# tsop_board.net
KiCad netlist of a schematic drawn in Altium Designer
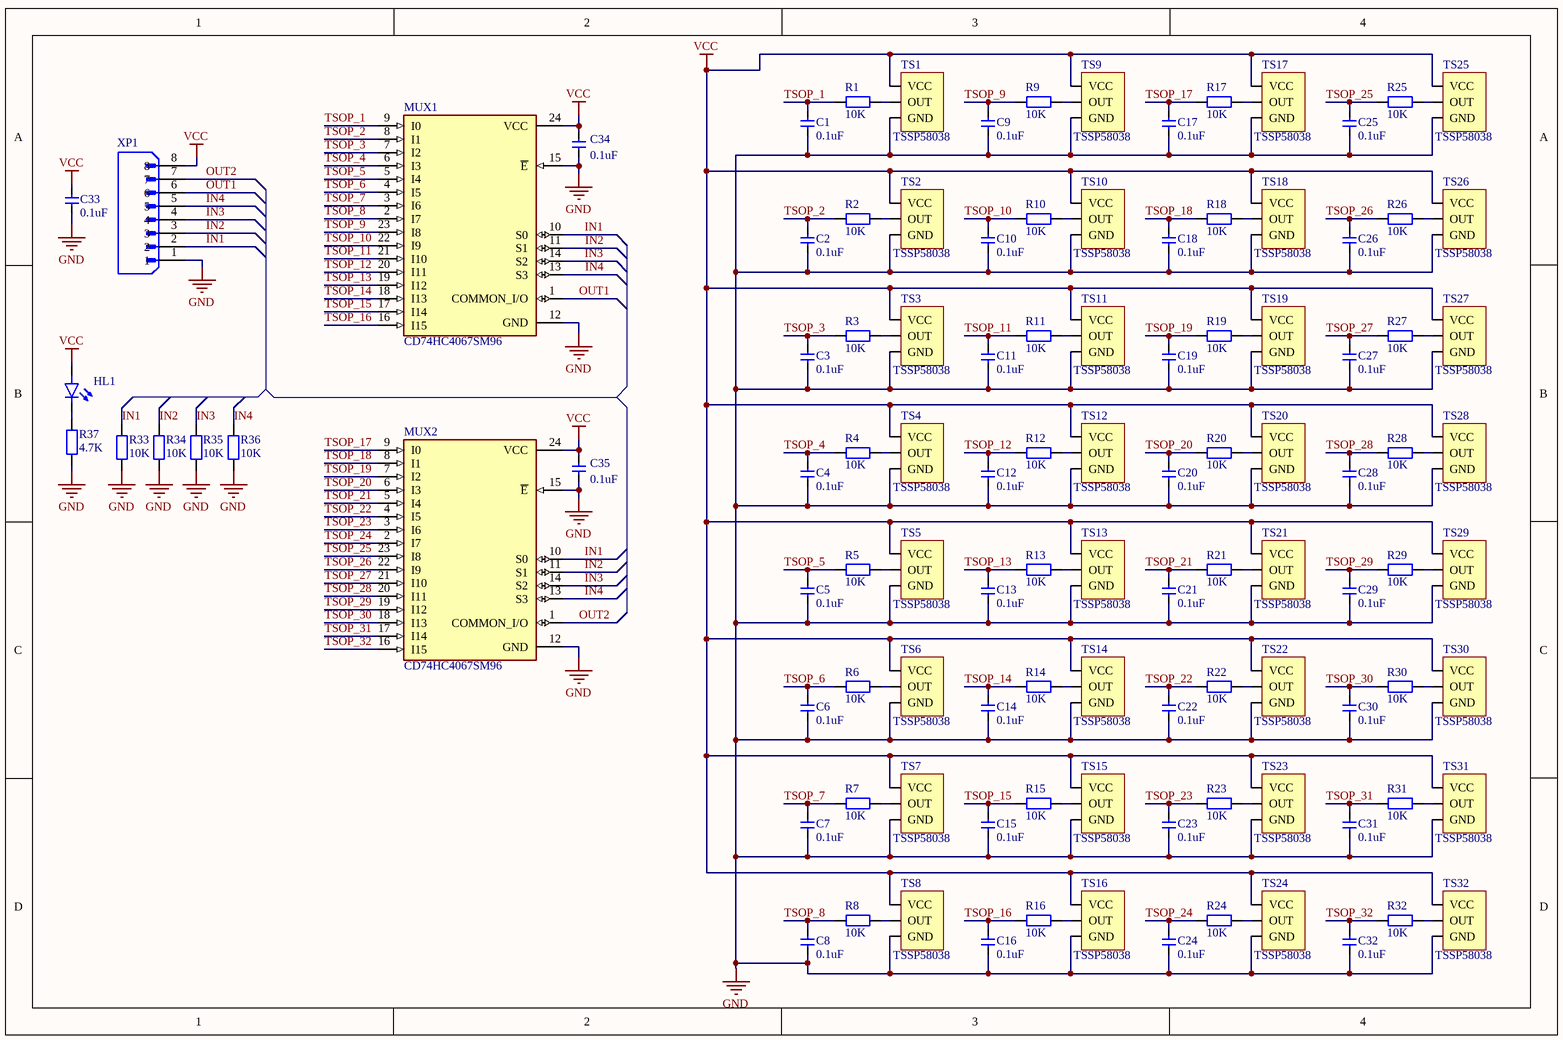
[diagram p0: tsop_board.SchDoc]

(export (version "E")
  (design (tool "Eeschema 10.0.6"))
  (components
    (comp (ref "C1")
      (value "0.1uF")
      (footprint "CAP0805")
      (description "Ceramic SMD Cap")
      (libsource (lib "Asterisk") (part "CAP Ceramic"))
    )
    (comp (ref "C2")
      (value "0.1uF")
      (footprint "CAP0805")
      (description "Ceramic SMD Cap")
      (libsource (lib "Asterisk") (part "CAP Ceramic"))
    )
    (comp (ref "C3")
      (value "0.1uF")
      (footprint "CAP0805")
      (description "Ceramic SMD Cap")
      (libsource (lib "Asterisk") (part "CAP Ceramic"))
    )
    (comp (ref "C4")
      (value "0.1uF")
      (footprint "CAP0805")
      (description "Ceramic SMD Cap")
      (libsource (lib "Asterisk") (part "CAP Ceramic"))
    )
    (comp (ref "C5")
      (value "0.1uF")
      (footprint "CAP0805")
      (description "Ceramic SMD Cap")
      (libsource (lib "Asterisk") (part "CAP Ceramic"))
    )
    (comp (ref "C6")
      (value "0.1uF")
      (footprint "CAP0805")
      (description "Ceramic SMD Cap")
      (libsource (lib "Asterisk") (part "CAP Ceramic"))
    )
    (comp (ref "C7")
      (value "0.1uF")
      (footprint "CAP0805")
      (description "Ceramic SMD Cap")
      (libsource (lib "Asterisk") (part "CAP Ceramic"))
    )
    (comp (ref "C8")
      (value "0.1uF")
      (footprint "CAP0805")
      (description "Ceramic SMD Cap")
      (libsource (lib "Asterisk") (part "CAP Ceramic"))
    )
    (comp (ref "C9")
      (value "0.1uF")
      (footprint "CAP0805")
      (description "Ceramic SMD Cap")
      (libsource (lib "Asterisk") (part "CAP Ceramic"))
    )
    (comp (ref "C10")
      (value "0.1uF")
      (footprint "CAP0805")
      (description "Ceramic SMD Cap")
      (libsource (lib "Asterisk") (part "CAP Ceramic"))
    )
    (comp (ref "C11")
      (value "0.1uF")
      (footprint "CAP0805")
      (description "Ceramic SMD Cap")
      (libsource (lib "Asterisk") (part "CAP Ceramic"))
    )
    (comp (ref "C12")
      (value "0.1uF")
      (footprint "CAP0805")
      (description "Ceramic SMD Cap")
      (libsource (lib "Asterisk") (part "CAP Ceramic"))
    )
    (comp (ref "C13")
      (value "0.1uF")
      (footprint "CAP0805")
      (description "Ceramic SMD Cap")
      (libsource (lib "Asterisk") (part "CAP Ceramic"))
    )
    (comp (ref "C14")
      (value "0.1uF")
      (footprint "CAP0805")
      (description "Ceramic SMD Cap")
      (libsource (lib "Asterisk") (part "CAP Ceramic"))
    )
    (comp (ref "C15")
      (value "0.1uF")
      (footprint "CAP0805")
      (description "Ceramic SMD Cap")
      (libsource (lib "Asterisk") (part "CAP Ceramic"))
    )
    (comp (ref "C16")
      (value "0.1uF")
      (footprint "CAP0805")
      (description "Ceramic SMD Cap")
      (libsource (lib "Asterisk") (part "CAP Ceramic"))
    )
    (comp (ref "C17")
      (value "0.1uF")
      (footprint "CAP0805")
      (description "Ceramic SMD Cap")
      (libsource (lib "Asterisk") (part "CAP Ceramic"))
    )
    (comp (ref "C18")
      (value "0.1uF")
      (footprint "CAP0805")
      (description "Ceramic SMD Cap")
      (libsource (lib "Asterisk") (part "CAP Ceramic"))
    )
    (comp (ref "C19")
      (value "0.1uF")
      (footprint "CAP0805")
      (description "Ceramic SMD Cap")
      (libsource (lib "Asterisk") (part "CAP Ceramic"))
    )
    (comp (ref "C20")
      (value "0.1uF")
      (footprint "CAP0805")
      (description "Ceramic SMD Cap")
      (libsource (lib "Asterisk") (part "CAP Ceramic"))
    )
    (comp (ref "C21")
      (value "0.1uF")
      (footprint "CAP0805")
      (description "Ceramic SMD Cap")
      (libsource (lib "Asterisk") (part "CAP Ceramic"))
    )
    (comp (ref "C22")
      (value "0.1uF")
      (footprint "CAP0805")
      (description "Ceramic SMD Cap")
      (libsource (lib "Asterisk") (part "CAP Ceramic"))
    )
    (comp (ref "C23")
      (value "0.1uF")
      (footprint "CAP0805")
      (description "Ceramic SMD Cap")
      (libsource (lib "Asterisk") (part "CAP Ceramic"))
    )
    (comp (ref "C24")
      (value "0.1uF")
      (footprint "CAP0805")
      (description "Ceramic SMD Cap")
      (libsource (lib "Asterisk") (part "CAP Ceramic"))
    )
    (comp (ref "C25")
      (value "0.1uF")
      (footprint "CAP0805")
      (description "Ceramic SMD Cap")
      (libsource (lib "Asterisk") (part "CAP Ceramic"))
    )
    (comp (ref "C26")
      (value "0.1uF")
      (footprint "CAP0805")
      (description "Ceramic SMD Cap")
      (libsource (lib "Asterisk") (part "CAP Ceramic"))
    )
    (comp (ref "C27")
      (value "0.1uF")
      (footprint "CAP0805")
      (description "Ceramic SMD Cap")
      (libsource (lib "Asterisk") (part "CAP Ceramic"))
    )
    (comp (ref "C28")
      (value "0.1uF")
      (footprint "CAP0805")
      (description "Ceramic SMD Cap")
      (libsource (lib "Asterisk") (part "CAP Ceramic"))
    )
    (comp (ref "C29")
      (value "0.1uF")
      (footprint "CAP0805")
      (description "Ceramic SMD Cap")
      (libsource (lib "Asterisk") (part "CAP Ceramic"))
    )
    (comp (ref "C30")
      (value "0.1uF")
      (footprint "CAP0805")
      (description "Ceramic SMD Cap")
      (libsource (lib "Asterisk") (part "CAP Ceramic"))
    )
    (comp (ref "C31")
      (value "0.1uF")
      (footprint "CAP0805")
      (description "Ceramic SMD Cap")
      (libsource (lib "Asterisk") (part "CAP Ceramic"))
    )
    (comp (ref "C32")
      (value "0.1uF")
      (footprint "CAP0805")
      (description "Ceramic SMD Cap")
      (libsource (lib "Asterisk") (part "CAP Ceramic"))
    )
    (comp (ref "C33")
      (value "0.1uF")
      (footprint "CAP0805")
      (description "Ceramic SMD Cap")
      (libsource (lib "Asterisk") (part "CAP Ceramic"))
    )
    (comp (ref "C34")
      (value "0.1uF")
      (footprint "CAP0805")
      (description "Ceramic SMD Cap")
      (libsource (lib "Asterisk") (part "CAP Ceramic"))
    )
    (comp (ref "C35")
      (value "0.1uF")
      (footprint "CAP0805")
      (description "Ceramic SMD Cap")
      (libsource (lib "Asterisk") (part "CAP Ceramic"))
    )
    (comp (ref "HL1")
      (value "Green")
      (footprint "LED0603_GREEN")
      (description "LED smd")
      (libsource (lib "Asterisk") (part "LED"))
    )
    (comp (ref "MUX1")
      (value "CD74HC4067SM96")
      (footprint "SSOP-24")
      (description "16-channel multiplexer")
      (libsource (lib "Asterisk") (part "CD74HC4067SM96"))
    )
    (comp (ref "MUX2")
      (value "CD74HC4067SM96")
      (footprint "SSOP-24")
      (description "16-channel multiplexer")
      (libsource (lib "Asterisk") (part "CD74HC4067SM96"))
    )
    (comp (ref "R1")
      (value "10K")
      (footprint "RES0805")
      (description "RES smd")
      (libsource (lib "Asterisk") (part "RES"))
    )
    (comp (ref "R2")
      (value "10K")
      (footprint "RES0805")
      (description "RES smd")
      (libsource (lib "Asterisk") (part "RES"))
    )
    (comp (ref "R3")
      (value "10K")
      (footprint "RES0805")
      (description "RES smd")
      (libsource (lib "Asterisk") (part "RES"))
    )
    (comp (ref "R4")
      (value "10K")
      (footprint "RES0805")
      (description "RES smd")
      (libsource (lib "Asterisk") (part "RES"))
    )
    (comp (ref "R5")
      (value "10K")
      (footprint "RES0805")
      (description "RES smd")
      (libsource (lib "Asterisk") (part "RES"))
    )
    (comp (ref "R6")
      (value "10K")
      (footprint "RES0805")
      (description "RES smd")
      (libsource (lib "Asterisk") (part "RES"))
    )
    (comp (ref "R7")
      (value "10K")
      (footprint "RES0805")
      (description "RES smd")
      (libsource (lib "Asterisk") (part "RES"))
    )
    (comp (ref "R8")
      (value "10K")
      (footprint "RES0805")
      (description "RES smd")
      (libsource (lib "Asterisk") (part "RES"))
    )
    (comp (ref "R9")
      (value "10K")
      (footprint "RES0805")
      (description "RES smd")
      (libsource (lib "") (part "RES_1"))
    )
    (comp (ref "R10")
      (value "10K")
      (footprint "RES0805")
      (description "RES smd")
      (libsource (lib "") (part "RES_1"))
    )
    (comp (ref "R11")
      (value "10K")
      (footprint "RES0805")
      (description "RES smd")
      (libsource (lib "") (part "RES_1"))
    )
    (comp (ref "R12")
      (value "10K")
      (footprint "RES0805")
      (description "RES smd")
      (libsource (lib "") (part "RES_1"))
    )
    (comp (ref "R13")
      (value "10K")
      (footprint "RES0805")
      (description "RES smd")
      (libsource (lib "") (part "RES_1"))
    )
    (comp (ref "R14")
      (value "10K")
      (footprint "RES0805")
      (description "RES smd")
      (libsource (lib "") (part "RES_1"))
    )
    (comp (ref "R15")
      (value "10K")
      (footprint "RES0805")
      (description "RES smd")
      (libsource (lib "") (part "RES_1"))
    )
    (comp (ref "R16")
      (value "10K")
      (footprint "RES0805")
      (description "RES smd")
      (libsource (lib "") (part "RES_1"))
    )
    (comp (ref "R17")
      (value "10K")
      (footprint "RES0805")
      (description "RES smd")
      (libsource (lib "Asterisk") (part "RES"))
    )
    (comp (ref "R18")
      (value "10K")
      (footprint "RES0805")
      (description "RES smd")
      (libsource (lib "Asterisk") (part "RES"))
    )
    (comp (ref "R19")
      (value "10K")
      (footprint "RES0805")
      (description "RES smd")
      (libsource (lib "Asterisk") (part "RES"))
    )
    (comp (ref "R20")
      (value "10K")
      (footprint "RES0805")
      (description "RES smd")
      (libsource (lib "Asterisk") (part "RES"))
    )
    (comp (ref "R21")
      (value "10K")
      (footprint "RES0805")
      (description "RES smd")
      (libsource (lib "Asterisk") (part "RES"))
    )
    (comp (ref "R22")
      (value "10K")
      (footprint "RES0805")
      (description "RES smd")
      (libsource (lib "Asterisk") (part "RES"))
    )
    (comp (ref "R23")
      (value "10K")
      (footprint "RES0805")
      (description "RES smd")
      (libsource (lib "Asterisk") (part "RES"))
    )
    (comp (ref "R24")
      (value "10K")
      (footprint "RES0805")
      (description "RES smd")
      (libsource (lib "Asterisk") (part "RES"))
    )
    (comp (ref "R25")
      (value "10K")
      (footprint "RES0805")
      (description "RES smd")
      (libsource (lib "Asterisk") (part "RES"))
    )
    (comp (ref "R26")
      (value "10K")
      (footprint "RES0805")
      (description "RES smd")
      (libsource (lib "Asterisk") (part "RES"))
    )
    (comp (ref "R27")
      (value "10K")
      (footprint "RES0805")
      (description "RES smd")
      (libsource (lib "Asterisk") (part "RES"))
    )
    (comp (ref "R28")
      (value "10K")
      (footprint "RES0805")
      (description "RES smd")
      (libsource (lib "Asterisk") (part "RES"))
    )
    (comp (ref "R29")
      (value "10K")
      (footprint "RES0805")
      (description "RES smd")
      (libsource (lib "Asterisk") (part "RES"))
    )
    (comp (ref "R30")
      (value "10K")
      (footprint "RES0805")
      (description "RES smd")
      (libsource (lib "Asterisk") (part "RES"))
    )
    (comp (ref "R31")
      (value "10K")
      (footprint "RES0805")
      (description "RES smd")
      (libsource (lib "Asterisk") (part "RES"))
    )
    (comp (ref "R32")
      (value "10K")
      (footprint "RES0805")
      (description "RES smd")
      (libsource (lib "Asterisk") (part "RES"))
    )
    (comp (ref "R33")
      (value "10K")
      (footprint "RES0805")
      (description "RES smd")
      (libsource (lib "Asterisk") (part "RES"))
    )
    (comp (ref "R34")
      (value "10K")
      (footprint "RES0805")
      (description "RES smd")
      (libsource (lib "Asterisk") (part "RES"))
    )
    (comp (ref "R35")
      (value "10K")
      (footprint "RES0805")
      (description "RES smd")
      (libsource (lib "Asterisk") (part "RES"))
    )
    (comp (ref "R36")
      (value "10K")
      (footprint "RES0805")
      (description "RES smd")
      (libsource (lib "Asterisk") (part "RES"))
    )
    (comp (ref "R37")
      (value "4.7K")
      (footprint "RES0805")
      (description "RES smd")
      (libsource (lib "Asterisk") (part "RES"))
    )
    (comp (ref "TS1")
      (value "TSSP58038")
      (footprint "TSSP58038 (clear)")
      (description "TSOP TSSP58038")
      (libsource (lib "Asterisk") (part "TSSP58038"))
    )
    (comp (ref "TS2")
      (value "TSSP58038")
      (footprint "TSSP58038 (clear)")
      (description "TSOP TSSP58038")
      (libsource (lib "Asterisk") (part "TSSP58038"))
    )
    (comp (ref "TS3")
      (value "TSSP58038")
      (footprint "TSSP58038 (clear)")
      (description "TSOP TSSP58038")
      (libsource (lib "Asterisk") (part "TSSP58038"))
    )
    (comp (ref "TS4")
      (value "TSSP58038")
      (footprint "TSSP58038 (clear)")
      (description "TSOP TSSP58038")
      (libsource (lib "Asterisk") (part "TSSP58038"))
    )
    (comp (ref "TS5")
      (value "TSSP58038")
      (footprint "TSSP58038 (clear)")
      (description "TSOP TSSP58038")
      (libsource (lib "Asterisk") (part "TSSP58038"))
    )
    (comp (ref "TS6")
      (value "TSSP58038")
      (footprint "TSSP58038 (clear)")
      (description "TSOP TSSP58038")
      (libsource (lib "Asterisk") (part "TSSP58038"))
    )
    (comp (ref "TS7")
      (value "TSSP58038")
      (footprint "TSSP58038 (clear)")
      (description "TSOP TSSP58038")
      (libsource (lib "Asterisk") (part "TSSP58038"))
    )
    (comp (ref "TS8")
      (value "TSSP58038")
      (footprint "TSSP58038 (clear)")
      (description "TSOP TSSP58038")
      (libsource (lib "Asterisk") (part "TSSP58038"))
    )
    (comp (ref "TS9")
      (value "TSSP58038")
      (footprint "TSSP58038 (clear)")
      (description "TSOP TSSP58038")
      (libsource (lib "Asterisk") (part "TSSP58038"))
    )
    (comp (ref "TS10")
      (value "TSSP58038")
      (footprint "TSSP58038 (clear)")
      (description "TSOP TSSP58038")
      (libsource (lib "Asterisk") (part "TSSP58038"))
    )
    (comp (ref "TS11")
      (value "TSSP58038")
      (footprint "TSSP58038 (clear)")
      (description "TSOP TSSP58038")
      (libsource (lib "Asterisk") (part "TSSP58038"))
    )
    (comp (ref "TS12")
      (value "TSSP58038")
      (footprint "TSSP58038 (clear)")
      (description "TSOP TSSP58038")
      (libsource (lib "Asterisk") (part "TSSP58038"))
    )
    (comp (ref "TS13")
      (value "TSSP58038")
      (footprint "TSSP58038 (clear)")
      (description "TSOP TSSP58038")
      (libsource (lib "Asterisk") (part "TSSP58038"))
    )
    (comp (ref "TS14")
      (value "TSSP58038")
      (footprint "TSSP58038 (clear)")
      (description "TSOP TSSP58038")
      (libsource (lib "Asterisk") (part "TSSP58038"))
    )
    (comp (ref "TS15")
      (value "TSSP58038")
      (footprint "TSSP58038 (clear)")
      (description "TSOP TSSP58038")
      (libsource (lib "Asterisk") (part "TSSP58038"))
    )
    (comp (ref "TS16")
      (value "TSSP58038")
      (footprint "TSSP58038 (clear)")
      (description "TSOP TSSP58038")
      (libsource (lib "Asterisk") (part "TSSP58038"))
    )
    (comp (ref "TS17")
      (value "TSSP58038")
      (footprint "TSSP58038 (clear)")
      (description "TSOP TSSP58038")
      (libsource (lib "Asterisk") (part "TSSP58038"))
    )
    (comp (ref "TS18")
      (value "TSSP58038")
      (footprint "TSSP58038 (clear)")
      (description "TSOP TSSP58038")
      (libsource (lib "Asterisk") (part "TSSP58038"))
    )
    (comp (ref "TS19")
      (value "TSSP58038")
      (footprint "TSSP58038 (clear)")
      (description "TSOP TSSP58038")
      (libsource (lib "Asterisk") (part "TSSP58038"))
    )
    (comp (ref "TS20")
      (value "TSSP58038")
      (footprint "TSSP58038 (clear)")
      (description "TSOP TSSP58038")
      (libsource (lib "Asterisk") (part "TSSP58038"))
    )
    (comp (ref "TS21")
      (value "TSSP58038")
      (footprint "TSSP58038 (clear)")
      (description "TSOP TSSP58038")
      (libsource (lib "Asterisk") (part "TSSP58038"))
    )
    (comp (ref "TS22")
      (value "TSSP58038")
      (footprint "TSSP58038 (clear)")
      (description "TSOP TSSP58038")
      (libsource (lib "Asterisk") (part "TSSP58038"))
    )
    (comp (ref "TS23")
      (value "TSSP58038")
      (footprint "TSSP58038 (clear)")
      (description "TSOP TSSP58038")
      (libsource (lib "Asterisk") (part "TSSP58038"))
    )
    (comp (ref "TS24")
      (value "TSSP58038")
      (footprint "TSSP58038 (clear)")
      (description "TSOP TSSP58038")
      (libsource (lib "Asterisk") (part "TSSP58038"))
    )
    (comp (ref "TS25")
      (value "TSSP58038")
      (footprint "TSSP58038 (clear)")
      (description "TSOP TSSP58038")
      (libsource (lib "Asterisk") (part "TSSP58038"))
    )
    (comp (ref "TS26")
      (value "TSSP58038")
      (footprint "TSSP58038 (clear)")
      (description "TSOP TSSP58038")
      (libsource (lib "Asterisk") (part "TSSP58038"))
    )
    (comp (ref "TS27")
      (value "TSSP58038")
      (footprint "TSSP58038 (clear)")
      (description "TSOP TSSP58038")
      (libsource (lib "Asterisk") (part "TSSP58038"))
    )
    (comp (ref "TS28")
      (value "TSSP58038")
      (footprint "TSSP58038 (clear)")
      (description "TSOP TSSP58038")
      (libsource (lib "Asterisk") (part "TSSP58038"))
    )
    (comp (ref "TS29")
      (value "TSSP58038")
      (footprint "TSSP58038 (clear)")
      (description "TSOP TSSP58038")
      (libsource (lib "Asterisk") (part "TSSP58038"))
    )
    (comp (ref "TS30")
      (value "TSSP58038")
      (footprint "TSSP58038 (clear)")
      (description "TSOP TSSP58038")
      (libsource (lib "Asterisk") (part "TSSP58038"))
    )
    (comp (ref "TS31")
      (value "TSSP58038")
      (footprint "TSSP58038 (clear)")
      (description "TSOP TSSP58038")
      (libsource (lib "Asterisk") (part "TSSP58038"))
    )
    (comp (ref "TS32")
      (value "TSSP58038")
      (footprint "TSSP58038 (clear)")
      (description "TSOP TSSP58038")
      (libsource (lib "Asterisk") (part "TSSP58038"))
    )
    (comp (ref "XP1")
      (value "JST_B8B-XH-A(LF)(SN)")
      (footprint "JST_XH-8")
      (description "TSOP Board")
      (libsource (lib "Asterisk") (part "JST-XH-8"))
    )
  )
  (nets
    (net (code "1") (name "/IN1") (class "Default")
      (node (ref "MUX1") (pin "10") (pinfunction "S0_10") (pintype "bidirectional"))
      (node (ref "MUX2") (pin "10") (pinfunction "S0_10") (pintype "bidirectional"))
      (node (ref "R33") (pin "2") (pinfunction "2_2") (pintype "passive"))
      (node (ref "XP1") (pin "2") (pinfunction "2_2") (pintype "passive"))
    )
    (net (code "2") (name "/IN2") (class "Default")
      (node (ref "MUX1") (pin "11") (pinfunction "S1_11") (pintype "bidirectional"))
      (node (ref "MUX2") (pin "11") (pinfunction "S1_11") (pintype "bidirectional"))
      (node (ref "R34") (pin "2") (pinfunction "2_2") (pintype "passive"))
      (node (ref "XP1") (pin "3") (pinfunction "3_3") (pintype "passive"))
    )
    (net (code "3") (name "/IN3") (class "Default")
      (node (ref "MUX1") (pin "14") (pinfunction "S2_14") (pintype "bidirectional"))
      (node (ref "MUX2") (pin "14") (pinfunction "S2_14") (pintype "bidirectional"))
      (node (ref "R35") (pin "2") (pinfunction "2_2") (pintype "passive"))
      (node (ref "XP1") (pin "4") (pinfunction "4_4") (pintype "passive"))
    )
    (net (code "4") (name "/IN4") (class "Default")
      (node (ref "MUX1") (pin "13") (pinfunction "S3_13") (pintype "bidirectional"))
      (node (ref "MUX2") (pin "13") (pinfunction "S3_13") (pintype "bidirectional"))
      (node (ref "R36") (pin "2") (pinfunction "2_2") (pintype "passive"))
      (node (ref "XP1") (pin "5") (pinfunction "5_5") (pintype "passive"))
    )
    (net (code "5") (name "/OUT1") (class "Default")
      (node (ref "MUX1") (pin "1") (pinfunction "COMMON_I/O_1") (pintype "bidirectional"))
      (node (ref "XP1") (pin "6") (pinfunction "6_6") (pintype "passive"))
    )
    (net (code "6") (name "/OUT2") (class "Default")
      (node (ref "MUX2") (pin "1") (pinfunction "COMMON_I/O_1") (pintype "bidirectional"))
      (node (ref "XP1") (pin "7") (pinfunction "7_7") (pintype "passive"))
    )
    (net (code "7") (name "/TSOP_1") (class "Default")
      (node (ref "C1") (pin "2") (pinfunction "2_2") (pintype "passive"))
      (node (ref "MUX1") (pin "9") (pinfunction "I0_9") (pintype "input"))
      (node (ref "R1") (pin "1") (pinfunction "1_1") (pintype "passive"))
    )
    (net (code "8") (name "/TSOP_2") (class "Default")
      (node (ref "C2") (pin "2") (pinfunction "2_2") (pintype "passive"))
      (node (ref "MUX1") (pin "8") (pinfunction "I1_8") (pintype "input"))
      (node (ref "R2") (pin "1") (pinfunction "1_1") (pintype "passive"))
    )
    (net (code "9") (name "/TSOP_3") (class "Default")
      (node (ref "C3") (pin "2") (pinfunction "2_2") (pintype "passive"))
      (node (ref "MUX1") (pin "7") (pinfunction "I2_7") (pintype "input"))
      (node (ref "R3") (pin "1") (pinfunction "1_1") (pintype "passive"))
    )
    (net (code "10") (name "/TSOP_4") (class "Default")
      (node (ref "C4") (pin "2") (pinfunction "2_2") (pintype "passive"))
      (node (ref "MUX1") (pin "6") (pinfunction "I3_6") (pintype "input"))
      (node (ref "R4") (pin "1") (pinfunction "1_1") (pintype "passive"))
    )
    (net (code "11") (name "/TSOP_5") (class "Default")
      (node (ref "C5") (pin "2") (pinfunction "2_2") (pintype "passive"))
      (node (ref "MUX1") (pin "5") (pinfunction "I4_5") (pintype "input"))
      (node (ref "R5") (pin "1") (pinfunction "1_1") (pintype "passive"))
    )
    (net (code "12") (name "/TSOP_6") (class "Default")
      (node (ref "C6") (pin "2") (pinfunction "2_2") (pintype "passive"))
      (node (ref "MUX1") (pin "4") (pinfunction "I5_4") (pintype "input"))
      (node (ref "R6") (pin "1") (pinfunction "1_1") (pintype "passive"))
    )
    (net (code "13") (name "/TSOP_7") (class "Default")
      (node (ref "C7") (pin "2") (pinfunction "2_2") (pintype "passive"))
      (node (ref "MUX1") (pin "3") (pinfunction "I6_3") (pintype "input"))
      (node (ref "R7") (pin "1") (pinfunction "1_1") (pintype "passive"))
    )
    (net (code "14") (name "/TSOP_8") (class "Default")
      (node (ref "C8") (pin "2") (pinfunction "2_2") (pintype "passive"))
      (node (ref "MUX1") (pin "2") (pinfunction "I7_2") (pintype "input"))
      (node (ref "R8") (pin "1") (pinfunction "1_1") (pintype "passive"))
    )
    (net (code "15") (name "/TSOP_9") (class "Default")
      (node (ref "C9") (pin "2") (pinfunction "2_2") (pintype "passive"))
      (node (ref "MUX1") (pin "23") (pinfunction "I8_23") (pintype "input"))
      (node (ref "R9") (pin "1") (pinfunction "1_1") (pintype "passive"))
    )
    (net (code "16") (name "/TSOP_10") (class "Default")
      (node (ref "C10") (pin "2") (pinfunction "2_2") (pintype "passive"))
      (node (ref "MUX1") (pin "22") (pinfunction "I9_22") (pintype "input"))
      (node (ref "R10") (pin "1") (pinfunction "1_1") (pintype "passive"))
    )
    (net (code "17") (name "/TSOP_11") (class "Default")
      (node (ref "C11") (pin "2") (pinfunction "2_2") (pintype "passive"))
      (node (ref "MUX1") (pin "21") (pinfunction "I10_21") (pintype "input"))
      (node (ref "R11") (pin "1") (pinfunction "1_1") (pintype "passive"))
    )
    (net (code "18") (name "/TSOP_12") (class "Default")
      (node (ref "C12") (pin "2") (pinfunction "2_2") (pintype "passive"))
      (node (ref "MUX1") (pin "20") (pinfunction "I11_20") (pintype "input"))
      (node (ref "R12") (pin "1") (pinfunction "1_1") (pintype "passive"))
    )
    (net (code "19") (name "/TSOP_13") (class "Default")
      (node (ref "C13") (pin "2") (pinfunction "2_2") (pintype "passive"))
      (node (ref "MUX1") (pin "19") (pinfunction "I12_19") (pintype "input"))
      (node (ref "R13") (pin "1") (pinfunction "1_1") (pintype "passive"))
    )
    (net (code "20") (name "/TSOP_14") (class "Default")
      (node (ref "C14") (pin "2") (pinfunction "2_2") (pintype "passive"))
      (node (ref "MUX1") (pin "18") (pinfunction "I13_18") (pintype "input"))
      (node (ref "R14") (pin "1") (pinfunction "1_1") (pintype "passive"))
    )
    (net (code "21") (name "/TSOP_15") (class "Default")
      (node (ref "C15") (pin "2") (pinfunction "2_2") (pintype "passive"))
      (node (ref "MUX1") (pin "17") (pinfunction "I14_17") (pintype "input"))
      (node (ref "R15") (pin "1") (pinfunction "1_1") (pintype "passive"))
    )
    (net (code "22") (name "/TSOP_16") (class "Default")
      (node (ref "C16") (pin "2") (pinfunction "2_2") (pintype "passive"))
      (node (ref "MUX1") (pin "16") (pinfunction "I15_16") (pintype "input"))
      (node (ref "R16") (pin "1") (pinfunction "1_1") (pintype "passive"))
    )
    (net (code "23") (name "/TSOP_17") (class "Default")
      (node (ref "C17") (pin "2") (pinfunction "2_2") (pintype "passive"))
      (node (ref "MUX2") (pin "9") (pinfunction "I0_9") (pintype "input"))
      (node (ref "R17") (pin "1") (pinfunction "1_1") (pintype "passive"))
    )
    (net (code "24") (name "/TSOP_18") (class "Default")
      (node (ref "C18") (pin "2") (pinfunction "2_2") (pintype "passive"))
      (node (ref "MUX2") (pin "8") (pinfunction "I1_8") (pintype "input"))
      (node (ref "R18") (pin "1") (pinfunction "1_1") (pintype "passive"))
    )
    (net (code "25") (name "/TSOP_19") (class "Default")
      (node (ref "C19") (pin "2") (pinfunction "2_2") (pintype "passive"))
      (node (ref "MUX2") (pin "7") (pinfunction "I2_7") (pintype "input"))
      (node (ref "R19") (pin "1") (pinfunction "1_1") (pintype "passive"))
    )
    (net (code "26") (name "/TSOP_20") (class "Default")
      (node (ref "C20") (pin "2") (pinfunction "2_2") (pintype "passive"))
      (node (ref "MUX2") (pin "6") (pinfunction "I3_6") (pintype "input"))
      (node (ref "R20") (pin "1") (pinfunction "1_1") (pintype "passive"))
    )
    (net (code "27") (name "/TSOP_21") (class "Default")
      (node (ref "C21") (pin "2") (pinfunction "2_2") (pintype "passive"))
      (node (ref "MUX2") (pin "5") (pinfunction "I4_5") (pintype "input"))
      (node (ref "R21") (pin "1") (pinfunction "1_1") (pintype "passive"))
    )
    (net (code "28") (name "/TSOP_22") (class "Default")
      (node (ref "C22") (pin "2") (pinfunction "2_2") (pintype "passive"))
      (node (ref "MUX2") (pin "4") (pinfunction "I5_4") (pintype "input"))
      (node (ref "R22") (pin "1") (pinfunction "1_1") (pintype "passive"))
    )
    (net (code "29") (name "/TSOP_23") (class "Default")
      (node (ref "C23") (pin "2") (pinfunction "2_2") (pintype "passive"))
      (node (ref "MUX2") (pin "3") (pinfunction "I6_3") (pintype "input"))
      (node (ref "R23") (pin "1") (pinfunction "1_1") (pintype "passive"))
    )
    (net (code "30") (name "/TSOP_24") (class "Default")
      (node (ref "C24") (pin "2") (pinfunction "2_2") (pintype "passive"))
      (node (ref "MUX2") (pin "2") (pinfunction "I7_2") (pintype "input"))
      (node (ref "R24") (pin "1") (pinfunction "1_1") (pintype "passive"))
    )
    (net (code "31") (name "/TSOP_25") (class "Default")
      (node (ref "C25") (pin "2") (pinfunction "2_2") (pintype "passive"))
      (node (ref "MUX2") (pin "23") (pinfunction "I8_23") (pintype "input"))
      (node (ref "R25") (pin "1") (pinfunction "1_1") (pintype "passive"))
    )
    (net (code "32") (name "/TSOP_26") (class "Default")
      (node (ref "C26") (pin "2") (pinfunction "2_2") (pintype "passive"))
      (node (ref "MUX2") (pin "22") (pinfunction "I9_22") (pintype "input"))
      (node (ref "R26") (pin "1") (pinfunction "1_1") (pintype "passive"))
    )
    (net (code "33") (name "/TSOP_27") (class "Default")
      (node (ref "C27") (pin "2") (pinfunction "2_2") (pintype "passive"))
      (node (ref "MUX2") (pin "21") (pinfunction "I10_21") (pintype "input"))
      (node (ref "R27") (pin "1") (pinfunction "1_1") (pintype "passive"))
    )
    (net (code "34") (name "/TSOP_28") (class "Default")
      (node (ref "C28") (pin "2") (pinfunction "2_2") (pintype "passive"))
      (node (ref "MUX2") (pin "20") (pinfunction "I11_20") (pintype "input"))
      (node (ref "R28") (pin "1") (pinfunction "1_1") (pintype "passive"))
    )
    (net (code "35") (name "/TSOP_29") (class "Default")
      (node (ref "C29") (pin "2") (pinfunction "2_2") (pintype "passive"))
      (node (ref "MUX2") (pin "19") (pinfunction "I12_19") (pintype "input"))
      (node (ref "R29") (pin "1") (pinfunction "1_1") (pintype "passive"))
    )
    (net (code "36") (name "/TSOP_30") (class "Default")
      (node (ref "C30") (pin "2") (pinfunction "2_2") (pintype "passive"))
      (node (ref "MUX2") (pin "18") (pinfunction "I13_18") (pintype "input"))
      (node (ref "R30") (pin "1") (pinfunction "1_1") (pintype "passive"))
    )
    (net (code "37") (name "/TSOP_31") (class "Default")
      (node (ref "C31") (pin "2") (pinfunction "2_2") (pintype "passive"))
      (node (ref "MUX2") (pin "17") (pinfunction "I14_17") (pintype "input"))
      (node (ref "R31") (pin "1") (pinfunction "1_1") (pintype "passive"))
    )
    (net (code "38") (name "/TSOP_32") (class "Default")
      (node (ref "C32") (pin "2") (pinfunction "2_2") (pintype "passive"))
      (node (ref "MUX2") (pin "16") (pinfunction "I15_16") (pintype "input"))
      (node (ref "R32") (pin "1") (pinfunction "1_1") (pintype "passive"))
    )
    (net (code "39") (name "GND") (class "Default")
      (node (ref "C1") (pin "1") (pinfunction "1_1") (pintype "passive"))
      (node (ref "C10") (pin "1") (pinfunction "1_1") (pintype "passive"))
      (node (ref "C11") (pin "1") (pinfunction "1_1") (pintype "passive"))
      (node (ref "C12") (pin "1") (pinfunction "1_1") (pintype "passive"))
      (node (ref "C13") (pin "1") (pinfunction "1_1") (pintype "passive"))
      (node (ref "C14") (pin "1") (pinfunction "1_1") (pintype "passive"))
      (node (ref "C15") (pin "1") (pinfunction "1_1") (pintype "passive"))
      (node (ref "C16") (pin "1") (pinfunction "1_1") (pintype "passive"))
      (node (ref "C17") (pin "1") (pinfunction "1_1") (pintype "passive"))
      (node (ref "C18") (pin "1") (pinfunction "1_1") (pintype "passive"))
      (node (ref "C19") (pin "1") (pinfunction "1_1") (pintype "passive"))
      (node (ref "C2") (pin "1") (pinfunction "1_1") (pintype "passive"))
      (node (ref "C20") (pin "1") (pinfunction "1_1") (pintype "passive"))
      (node (ref "C21") (pin "1") (pinfunction "1_1") (pintype "passive"))
      (node (ref "C22") (pin "1") (pinfunction "1_1") (pintype "passive"))
      (node (ref "C23") (pin "1") (pinfunction "1_1") (pintype "passive"))
      (node (ref "C24") (pin "1") (pinfunction "1_1") (pintype "passive"))
      (node (ref "C25") (pin "1") (pinfunction "1_1") (pintype "passive"))
      (node (ref "C26") (pin "1") (pinfunction "1_1") (pintype "passive"))
      (node (ref "C27") (pin "1") (pinfunction "1_1") (pintype "passive"))
      (node (ref "C28") (pin "1") (pinfunction "1_1") (pintype "passive"))
      (node (ref "C29") (pin "1") (pinfunction "1_1") (pintype "passive"))
      (node (ref "C3") (pin "1") (pinfunction "1_1") (pintype "passive"))
      (node (ref "C30") (pin "1") (pinfunction "1_1") (pintype "passive"))
      (node (ref "C31") (pin "1") (pinfunction "1_1") (pintype "passive"))
      (node (ref "C32") (pin "1") (pinfunction "1_1") (pintype "passive"))
      (node (ref "C33") (pin "1") (pinfunction "1_1") (pintype "passive"))
      (node (ref "C34") (pin "1") (pinfunction "1_1") (pintype "passive"))
      (node (ref "C35") (pin "1") (pinfunction "1_1") (pintype "passive"))
      (node (ref "C4") (pin "1") (pinfunction "1_1") (pintype "passive"))
      (node (ref "C5") (pin "1") (pinfunction "1_1") (pintype "passive"))
      (node (ref "C6") (pin "1") (pinfunction "1_1") (pintype "passive"))
      (node (ref "C7") (pin "1") (pinfunction "1_1") (pintype "passive"))
      (node (ref "C8") (pin "1") (pinfunction "1_1") (pintype "passive"))
      (node (ref "C9") (pin "1") (pinfunction "1_1") (pintype "passive"))
      (node (ref "MUX1") (pin "12") (pinfunction "GND_12") (pintype "power_in"))
      (node (ref "MUX1") (pin "15") (pinfunction "~{E}_15") (pintype "input"))
      (node (ref "MUX2") (pin "12") (pinfunction "GND_12") (pintype "power_in"))
      (node (ref "MUX2") (pin "15") (pinfunction "~{E}_15") (pintype "input"))
      (node (ref "R33") (pin "1") (pinfunction "1_1") (pintype "passive"))
      (node (ref "R34") (pin "1") (pinfunction "1_1") (pintype "passive"))
      (node (ref "R35") (pin "1") (pinfunction "1_1") (pintype "passive"))
      (node (ref "R36") (pin "1") (pinfunction "1_1") (pintype "passive"))
      (node (ref "R37") (pin "1") (pinfunction "1_1") (pintype "passive"))
      (node (ref "TS1") (pin "2") (pinfunction "GND_2") (pintype "passive"))
      (node (ref "TS10") (pin "2") (pinfunction "GND_2") (pintype "passive"))
      (node (ref "TS11") (pin "2") (pinfunction "GND_2") (pintype "passive"))
      (node (ref "TS12") (pin "2") (pinfunction "GND_2") (pintype "passive"))
      (node (ref "TS13") (pin "2") (pinfunction "GND_2") (pintype "passive"))
      (node (ref "TS14") (pin "2") (pinfunction "GND_2") (pintype "passive"))
      (node (ref "TS15") (pin "2") (pinfunction "GND_2") (pintype "passive"))
      (node (ref "TS16") (pin "2") (pinfunction "GND_2") (pintype "passive"))
      (node (ref "TS17") (pin "2") (pinfunction "GND_2") (pintype "passive"))
      (node (ref "TS18") (pin "2") (pinfunction "GND_2") (pintype "passive"))
      (node (ref "TS19") (pin "2") (pinfunction "GND_2") (pintype "passive"))
      (node (ref "TS2") (pin "2") (pinfunction "GND_2") (pintype "passive"))
      (node (ref "TS20") (pin "2") (pinfunction "GND_2") (pintype "passive"))
      (node (ref "TS21") (pin "2") (pinfunction "GND_2") (pintype "passive"))
      (node (ref "TS22") (pin "2") (pinfunction "GND_2") (pintype "passive"))
      (node (ref "TS23") (pin "2") (pinfunction "GND_2") (pintype "passive"))
      (node (ref "TS24") (pin "2") (pinfunction "GND_2") (pintype "passive"))
      (node (ref "TS25") (pin "2") (pinfunction "GND_2") (pintype "passive"))
      (node (ref "TS26") (pin "2") (pinfunction "GND_2") (pintype "passive"))
      (node (ref "TS27") (pin "2") (pinfunction "GND_2") (pintype "passive"))
      (node (ref "TS28") (pin "2") (pinfunction "GND_2") (pintype "passive"))
      (node (ref "TS29") (pin "2") (pinfunction "GND_2") (pintype "passive"))
      (node (ref "TS3") (pin "2") (pinfunction "GND_2") (pintype "passive"))
      (node (ref "TS30") (pin "2") (pinfunction "GND_2") (pintype "passive"))
      (node (ref "TS31") (pin "2") (pinfunction "GND_2") (pintype "passive"))
      (node (ref "TS32") (pin "2") (pinfunction "GND_2") (pintype "passive"))
      (node (ref "TS4") (pin "2") (pinfunction "GND_2") (pintype "passive"))
      (node (ref "TS5") (pin "2") (pinfunction "GND_2") (pintype "passive"))
      (node (ref "TS6") (pin "2") (pinfunction "GND_2") (pintype "passive"))
      (node (ref "TS7") (pin "2") (pinfunction "GND_2") (pintype "passive"))
      (node (ref "TS8") (pin "2") (pinfunction "GND_2") (pintype "passive"))
      (node (ref "TS9") (pin "2") (pinfunction "GND_2") (pintype "passive"))
      (node (ref "XP1") (pin "1") (pinfunction "1_1") (pintype "passive"))
    )
    (net (code "40") (name "Net-(HL1-K)") (class "Default")
      (node (ref "HL1") (pin "1") (pinfunction "K_1") (pintype "passive"))
      (node (ref "R37") (pin "2") (pinfunction "2_2") (pintype "passive"))
    )
    (net (code "41") (name "Net-(TS1-OUT)") (class "Default")
      (node (ref "R1") (pin "2") (pinfunction "2_2") (pintype "passive"))
      (node (ref "TS1") (pin "3") (pinfunction "OUT_3") (pintype "passive"))
    )
    (net (code "42") (name "Net-(TS2-OUT)") (class "Default")
      (node (ref "R2") (pin "2") (pinfunction "2_2") (pintype "passive"))
      (node (ref "TS2") (pin "3") (pinfunction "OUT_3") (pintype "passive"))
    )
    (net (code "43") (name "Net-(TS3-OUT)") (class "Default")
      (node (ref "R3") (pin "2") (pinfunction "2_2") (pintype "passive"))
      (node (ref "TS3") (pin "3") (pinfunction "OUT_3") (pintype "passive"))
    )
    (net (code "44") (name "Net-(TS4-OUT)") (class "Default")
      (node (ref "R4") (pin "2") (pinfunction "2_2") (pintype "passive"))
      (node (ref "TS4") (pin "3") (pinfunction "OUT_3") (pintype "passive"))
    )
    (net (code "45") (name "Net-(TS5-OUT)") (class "Default")
      (node (ref "R5") (pin "2") (pinfunction "2_2") (pintype "passive"))
      (node (ref "TS5") (pin "3") (pinfunction "OUT_3") (pintype "passive"))
    )
    (net (code "46") (name "Net-(TS6-OUT)") (class "Default")
      (node (ref "R6") (pin "2") (pinfunction "2_2") (pintype "passive"))
      (node (ref "TS6") (pin "3") (pinfunction "OUT_3") (pintype "passive"))
    )
    (net (code "47") (name "Net-(TS7-OUT)") (class "Default")
      (node (ref "R7") (pin "2") (pinfunction "2_2") (pintype "passive"))
      (node (ref "TS7") (pin "3") (pinfunction "OUT_3") (pintype "passive"))
    )
    (net (code "48") (name "Net-(TS8-OUT)") (class "Default")
      (node (ref "R8") (pin "2") (pinfunction "2_2") (pintype "passive"))
      (node (ref "TS8") (pin "3") (pinfunction "OUT_3") (pintype "passive"))
    )
    (net (code "49") (name "Net-(TS9-OUT)") (class "Default")
      (node (ref "R9") (pin "2") (pinfunction "2_2") (pintype "passive"))
      (node (ref "TS9") (pin "3") (pinfunction "OUT_3") (pintype "passive"))
    )
    (net (code "50") (name "Net-(TS10-OUT)") (class "Default")
      (node (ref "R10") (pin "2") (pinfunction "2_2") (pintype "passive"))
      (node (ref "TS10") (pin "3") (pinfunction "OUT_3") (pintype "passive"))
    )
    (net (code "51") (name "Net-(TS11-OUT)") (class "Default")
      (node (ref "R11") (pin "2") (pinfunction "2_2") (pintype "passive"))
      (node (ref "TS11") (pin "3") (pinfunction "OUT_3") (pintype "passive"))
    )
    (net (code "52") (name "Net-(TS12-OUT)") (class "Default")
      (node (ref "R12") (pin "2") (pinfunction "2_2") (pintype "passive"))
      (node (ref "TS12") (pin "3") (pinfunction "OUT_3") (pintype "passive"))
    )
    (net (code "53") (name "Net-(TS13-OUT)") (class "Default")
      (node (ref "R13") (pin "2") (pinfunction "2_2") (pintype "passive"))
      (node (ref "TS13") (pin "3") (pinfunction "OUT_3") (pintype "passive"))
    )
    (net (code "54") (name "Net-(TS14-OUT)") (class "Default")
      (node (ref "R14") (pin "2") (pinfunction "2_2") (pintype "passive"))
      (node (ref "TS14") (pin "3") (pinfunction "OUT_3") (pintype "passive"))
    )
    (net (code "55") (name "Net-(TS15-OUT)") (class "Default")
      (node (ref "R15") (pin "2") (pinfunction "2_2") (pintype "passive"))
      (node (ref "TS15") (pin "3") (pinfunction "OUT_3") (pintype "passive"))
    )
    (net (code "56") (name "Net-(TS16-OUT)") (class "Default")
      (node (ref "R16") (pin "2") (pinfunction "2_2") (pintype "passive"))
      (node (ref "TS16") (pin "3") (pinfunction "OUT_3") (pintype "passive"))
    )
    (net (code "57") (name "Net-(TS17-OUT)") (class "Default")
      (node (ref "R17") (pin "2") (pinfunction "2_2") (pintype "passive"))
      (node (ref "TS17") (pin "3") (pinfunction "OUT_3") (pintype "passive"))
    )
    (net (code "58") (name "Net-(TS18-OUT)") (class "Default")
      (node (ref "R18") (pin "2") (pinfunction "2_2") (pintype "passive"))
      (node (ref "TS18") (pin "3") (pinfunction "OUT_3") (pintype "passive"))
    )
    (net (code "59") (name "Net-(TS19-OUT)") (class "Default")
      (node (ref "R19") (pin "2") (pinfunction "2_2") (pintype "passive"))
      (node (ref "TS19") (pin "3") (pinfunction "OUT_3") (pintype "passive"))
    )
    (net (code "60") (name "Net-(TS20-OUT)") (class "Default")
      (node (ref "R20") (pin "2") (pinfunction "2_2") (pintype "passive"))
      (node (ref "TS20") (pin "3") (pinfunction "OUT_3") (pintype "passive"))
    )
    (net (code "61") (name "Net-(TS21-OUT)") (class "Default")
      (node (ref "R21") (pin "2") (pinfunction "2_2") (pintype "passive"))
      (node (ref "TS21") (pin "3") (pinfunction "OUT_3") (pintype "passive"))
    )
    (net (code "62") (name "Net-(TS22-OUT)") (class "Default")
      (node (ref "R22") (pin "2") (pinfunction "2_2") (pintype "passive"))
      (node (ref "TS22") (pin "3") (pinfunction "OUT_3") (pintype "passive"))
    )
    (net (code "63") (name "Net-(TS23-OUT)") (class "Default")
      (node (ref "R23") (pin "2") (pinfunction "2_2") (pintype "passive"))
      (node (ref "TS23") (pin "3") (pinfunction "OUT_3") (pintype "passive"))
    )
    (net (code "64") (name "Net-(TS24-OUT)") (class "Default")
      (node (ref "R24") (pin "2") (pinfunction "2_2") (pintype "passive"))
      (node (ref "TS24") (pin "3") (pinfunction "OUT_3") (pintype "passive"))
    )
    (net (code "65") (name "Net-(TS25-OUT)") (class "Default")
      (node (ref "R25") (pin "2") (pinfunction "2_2") (pintype "passive"))
      (node (ref "TS25") (pin "3") (pinfunction "OUT_3") (pintype "passive"))
    )
    (net (code "66") (name "Net-(TS26-OUT)") (class "Default")
      (node (ref "R26") (pin "2") (pinfunction "2_2") (pintype "passive"))
      (node (ref "TS26") (pin "3") (pinfunction "OUT_3") (pintype "passive"))
    )
    (net (code "67") (name "Net-(TS27-OUT)") (class "Default")
      (node (ref "R27") (pin "2") (pinfunction "2_2") (pintype "passive"))
      (node (ref "TS27") (pin "3") (pinfunction "OUT_3") (pintype "passive"))
    )
    (net (code "68") (name "Net-(TS28-OUT)") (class "Default")
      (node (ref "R28") (pin "2") (pinfunction "2_2") (pintype "passive"))
      (node (ref "TS28") (pin "3") (pinfunction "OUT_3") (pintype "passive"))
    )
    (net (code "69") (name "Net-(TS29-OUT)") (class "Default")
      (node (ref "R29") (pin "2") (pinfunction "2_2") (pintype "passive"))
      (node (ref "TS29") (pin "3") (pinfunction "OUT_3") (pintype "passive"))
    )
    (net (code "70") (name "Net-(TS30-OUT)") (class "Default")
      (node (ref "R30") (pin "2") (pinfunction "2_2") (pintype "passive"))
      (node (ref "TS30") (pin "3") (pinfunction "OUT_3") (pintype "passive"))
    )
    (net (code "71") (name "Net-(TS31-OUT)") (class "Default")
      (node (ref "R31") (pin "2") (pinfunction "2_2") (pintype "passive"))
      (node (ref "TS31") (pin "3") (pinfunction "OUT_3") (pintype "passive"))
    )
    (net (code "72") (name "Net-(TS32-OUT)") (class "Default")
      (node (ref "R32") (pin "2") (pinfunction "2_2") (pintype "passive"))
      (node (ref "TS32") (pin "3") (pinfunction "OUT_3") (pintype "passive"))
    )
    (net (code "73") (name "VCC") (class "Default")
      (node (ref "C33") (pin "2") (pinfunction "2_2") (pintype "passive"))
      (node (ref "C34") (pin "2") (pinfunction "2_2") (pintype "passive"))
      (node (ref "C35") (pin "2") (pinfunction "2_2") (pintype "passive"))
      (node (ref "HL1") (pin "2") (pinfunction "A_2") (pintype "passive"))
      (node (ref "MUX1") (pin "24") (pinfunction "VCC_24") (pintype "power_in"))
      (node (ref "MUX2") (pin "24") (pinfunction "VCC_24") (pintype "power_in"))
      (node (ref "TS1") (pin "1") (pinfunction "VCC_1") (pintype "passive"))
      (node (ref "TS10") (pin "1") (pinfunction "VCC_1") (pintype "passive"))
      (node (ref "TS11") (pin "1") (pinfunction "VCC_1") (pintype "passive"))
      (node (ref "TS12") (pin "1") (pinfunction "VCC_1") (pintype "passive"))
      (node (ref "TS13") (pin "1") (pinfunction "VCC_1") (pintype "passive"))
      (node (ref "TS14") (pin "1") (pinfunction "VCC_1") (pintype "passive"))
      (node (ref "TS15") (pin "1") (pinfunction "VCC_1") (pintype "passive"))
      (node (ref "TS16") (pin "1") (pinfunction "VCC_1") (pintype "passive"))
      (node (ref "TS17") (pin "1") (pinfunction "VCC_1") (pintype "passive"))
      (node (ref "TS18") (pin "1") (pinfunction "VCC_1") (pintype "passive"))
      (node (ref "TS19") (pin "1") (pinfunction "VCC_1") (pintype "passive"))
      (node (ref "TS2") (pin "1") (pinfunction "VCC_1") (pintype "passive"))
      (node (ref "TS20") (pin "1") (pinfunction "VCC_1") (pintype "passive"))
      (node (ref "TS21") (pin "1") (pinfunction "VCC_1") (pintype "passive"))
      (node (ref "TS22") (pin "1") (pinfunction "VCC_1") (pintype "passive"))
      (node (ref "TS23") (pin "1") (pinfunction "VCC_1") (pintype "passive"))
      (node (ref "TS24") (pin "1") (pinfunction "VCC_1") (pintype "passive"))
      (node (ref "TS25") (pin "1") (pinfunction "VCC_1") (pintype "passive"))
      (node (ref "TS26") (pin "1") (pinfunction "VCC_1") (pintype "passive"))
      (node (ref "TS27") (pin "1") (pinfunction "VCC_1") (pintype "passive"))
      (node (ref "TS28") (pin "1") (pinfunction "VCC_1") (pintype "passive"))
      (node (ref "TS29") (pin "1") (pinfunction "VCC_1") (pintype "passive"))
      (node (ref "TS3") (pin "1") (pinfunction "VCC_1") (pintype "passive"))
      (node (ref "TS30") (pin "1") (pinfunction "VCC_1") (pintype "passive"))
      (node (ref "TS31") (pin "1") (pinfunction "VCC_1") (pintype "passive"))
      (node (ref "TS32") (pin "1") (pinfunction "VCC_1") (pintype "passive"))
      (node (ref "TS4") (pin "1") (pinfunction "VCC_1") (pintype "passive"))
      (node (ref "TS5") (pin "1") (pinfunction "VCC_1") (pintype "passive"))
      (node (ref "TS6") (pin "1") (pinfunction "VCC_1") (pintype "passive"))
      (node (ref "TS7") (pin "1") (pinfunction "VCC_1") (pintype "passive"))
      (node (ref "TS8") (pin "1") (pinfunction "VCC_1") (pintype "passive"))
      (node (ref "TS9") (pin "1") (pinfunction "VCC_1") (pintype "passive"))
      (node (ref "XP1") (pin "8") (pinfunction "8_8") (pintype "passive"))
    )
  )
)
